# LED_driver_sch.net
KiCad netlist of a schematic drawn in Altium Designer
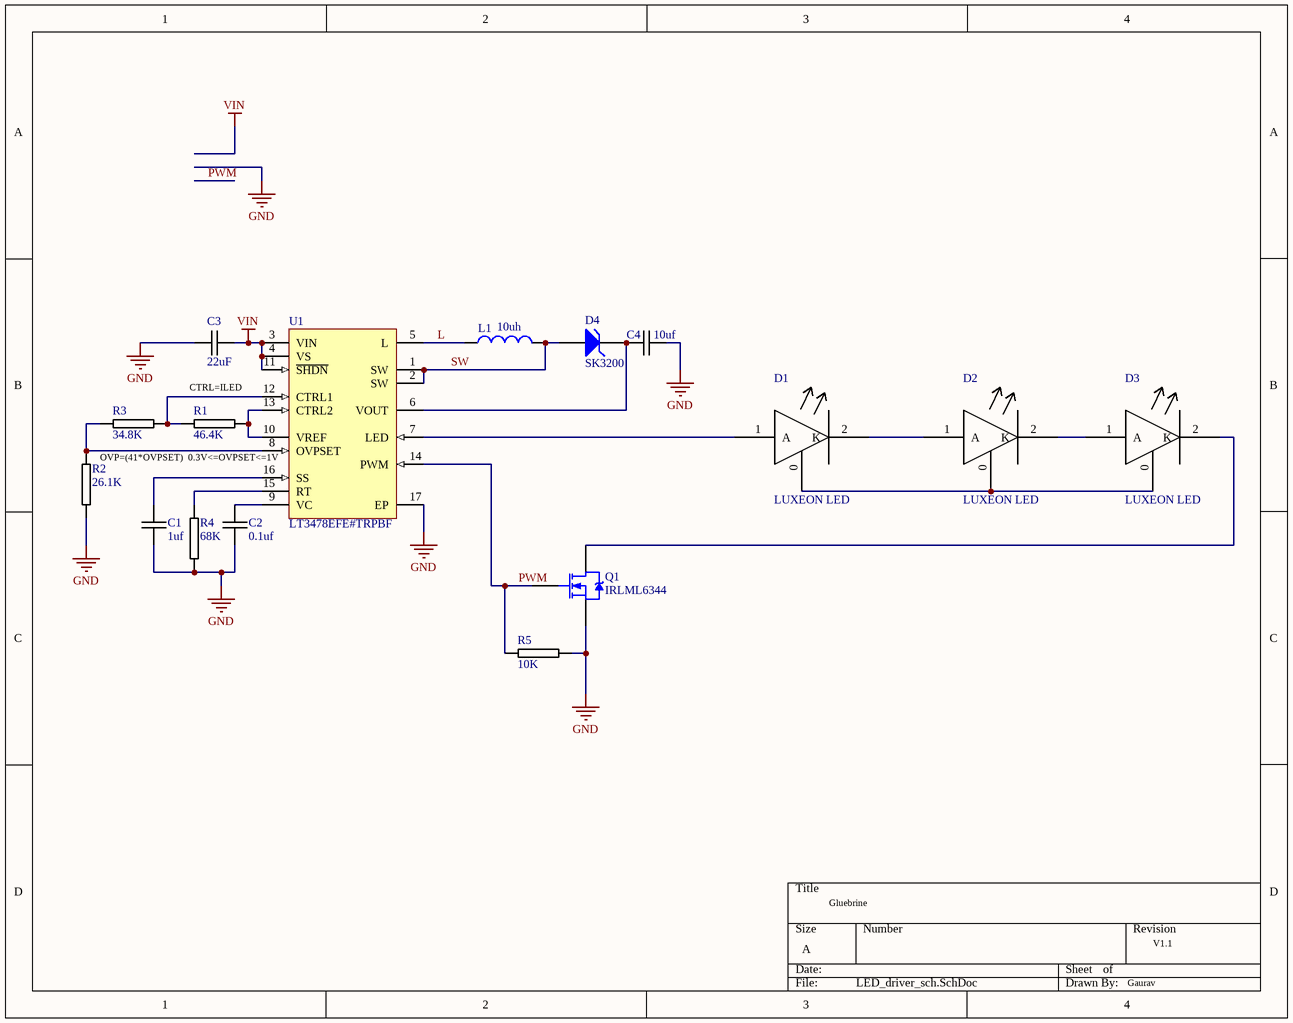
[diagram p0: LED_driver_sch.SchDoc]

(export (version "E")
  (design (tool "Eeschema 10.0.6"))
  (components
    (comp (ref "C1")
      (value "1uf")
      (footprint "0805C-TBD")
      (description "CAPACITOR 0805 CERAMIC VALUE TO BE DETERMINED")
      (libsource (lib "Generic") (part "0805C-TBD"))
    )
    (comp (ref "C2")
      (value "0.1uf")
      (footprint "0805C-TBD")
      (description "CAPACITOR 0805 CERAMIC VALUE TO BE DETERMINED")
      (libsource (lib "Generic") (part "0805C-TBD"))
    )
    (comp (ref "C3")
      (value "22uF")
      (footprint "1210C-GENERIC")
      (description "GENERIC CAPACITOR NON POLARISED 1210")
      (fields
        (field (name "MANUFACTURER") "Panasonic - ECG")
        (field (name "MANUFACTURER PART NUMBER") "ECJ-4YB0J226M")
      )
      (libsource (lib "Generic") (part "1210C-22UF-6V3-X5R-PAN"))
    )
    (comp (ref "C4")
      (value "10uf")
      (footprint "1210C-GENERIC")
      (description "GENERIC CAPACITOR NON POLARISED 1210")
      (fields
        (field (name "MANUFACTURER") "Panasonic - ECG")
        (field (name "MANUFACTURER PART NUMBER") "ECJ-4YB0J226M")
      )
      (libsource (lib "Generic") (part "1210C-22UF-6V3-X5R-PAN"))
    )
    (comp (ref "D1")
      (value "LUXEON LED")
      (footprint "LUXEON")
      (libsource (lib "philips_led") (part "LMX-PWC2"))
    )
    (comp (ref "D2")
      (value "LUXEON LED")
      (footprint "LUXEON")
      (libsource (lib "philips_led") (part "LMX-PWC2"))
    )
    (comp (ref "D3")
      (value "LUXEON LED")
      (footprint "LUXEON")
      (libsource (lib "philips_led") (part "LMX-PWC2"))
    )
    (comp (ref "D4") (value "SK3200") (footprint "SK3200") (libsource (lib "diode") (part "SK3200")))
    (comp (ref "L1") (value "10uh") (footprint "SRR1280A") (libsource (lib "Inductor") (part "inductor_smd")))
    (comp (ref "Q1")
      (value "IRLML6344")
      (footprint "SOT-23_N")
      (description "HEXFET Power MOSFET")
      (fields (field (name "PUBLISHER") "Altium Limited"))
      (libsource (lib "IR Discrete MOSFET - Power") (part "IRLML2402"))
    )
    (comp (ref "R1")
      (value "46.4K")
      (footprint "0805R-TBD")
      (description "RESISTOR 0805 VALUE TO BE DETERMINED")
      (libsource (lib "Generic") (part "0805R-TBD"))
    )
    (comp (ref "R2")
      (value "26.1K")
      (footprint "0805R-TBD")
      (description "RESISTOR 0805 VALUE TO BE DETERMINED")
      (libsource (lib "Generic") (part "0805R-TBD"))
    )
    (comp (ref "R3")
      (value "34.8K")
      (footprint "0805R-TBD")
      (description "RESISTOR 0805 VALUE TO BE DETERMINED")
      (libsource (lib "Generic") (part "0805R-TBD"))
    )
    (comp (ref "R4")
      (value "68K")
      (footprint "0805R-TBD")
      (description "RESISTOR 0805 VALUE TO BE DETERMINED")
      (libsource (lib "Generic") (part "0805R-TBD"))
    )
    (comp (ref "R5")
      (value "10K")
      (footprint "0603R-10K")
      (description "GENERIC RESISTOR 0603")
      (fields (field (name "MANUFACTURER") "Stackpole Electronics Inc") (field (name "TOLERANCE") "±1%"))
      (libsource (lib "Generic") (part "0603R-10K"))
    )
    (comp (ref "U1")
      (value "LT3478EFE#TRPBF")
      (footprint "LT-FE-16-EPV-BC_N")
      (fields (field (name "MANUFACTURER") "Linear Technology"))
      (libsource (lib "Linear Technology Power Management LED Driver ICs") (part "LT3478EFE#TRPBF"))
    )
  )
  (nets
    (net (code "1") (name "/L") (class "Default")
      (node (ref "L1") (pin "1") (pinfunction "1_1") (pintype "passive"))
      (node (ref "U1") (pin "5") (pinfunction "L_5") (pintype "power_in"))
    )
    (net (code "2") (name "/PWM") (class "Default")
      (node (ref "Q1") (pin "1") (pinfunction "G_1") (pintype "passive"))
      (node (ref "R5") (pin "1") (pintype "passive"))
      (node (ref "U1") (pin "14") (pinfunction "PWM_14") (pintype "input"))
    )
    (net (code "3") (name "/SW") (class "Default")
      (node (ref "D4") (pin "1") (pinfunction "A_1") (pintype "passive"))
      (node (ref "L1") (pin "2") (pinfunction "2_2") (pintype "passive"))
      (node (ref "U1") (pin "1") (pinfunction "SW_1") (pintype "power_in"))
      (node (ref "U1") (pin "2") (pinfunction "SW_2") (pintype "power_in"))
    )
    (net (code "4") (name "GND") (class "Default")
      (node (ref "C1") (pin "1") (pintype "passive"))
      (node (ref "C2") (pin "1") (pintype "passive"))
      (node (ref "C3") (pin "2") (pintype "passive"))
      (node (ref "C4") (pin "2") (pintype "passive"))
      (node (ref "Q1") (pin "2") (pinfunction "S_2") (pintype "passive"))
      (node (ref "R2") (pin "2") (pintype "passive"))
      (node (ref "R4") (pin "2") (pintype "passive"))
      (node (ref "R5") (pin "2") (pintype "passive"))
      (node (ref "U1") (pin "17") (pinfunction "EP_17") (pintype "power_in"))
    )
    (net (code "5") (name "Net-(D1-A)") (class "Default")
      (node (ref "D1") (pin "1") (pinfunction "A_1") (pintype "power_in"))
      (node (ref "U1") (pin "7") (pinfunction "LED_7") (pintype "input"))
    )
    (net (code "6") (name "Net-(D1-K)") (class "Default")
      (node (ref "D1") (pin "2") (pinfunction "K_2") (pintype "power_in"))
      (node (ref "D2") (pin "1") (pinfunction "A_1") (pintype "power_in"))
    )
    (net (code "7") (name "Net-(D1-TH)") (class "Default")
      (node (ref "D1") (pin "0") (pinfunction "TH_0") (pintype "passive"))
      (node (ref "D2") (pin "0") (pinfunction "TH_0") (pintype "passive"))
      (node (ref "D3") (pin "0") (pinfunction "TH_0") (pintype "passive"))
    )
    (net (code "8") (name "Net-(D2-K)") (class "Default")
      (node (ref "D2") (pin "2") (pinfunction "K_2") (pintype "power_in"))
      (node (ref "D3") (pin "1") (pinfunction "A_1") (pintype "power_in"))
    )
    (net (code "9") (name "Net-(D3-K)") (class "Default")
      (node (ref "D3") (pin "2") (pinfunction "K_2") (pintype "power_in"))
      (node (ref "Q1") (pin "3") (pinfunction "D_3") (pintype "passive"))
    )
    (net (code "10") (name "Net-(D4-K)") (class "Default")
      (node (ref "C4") (pin "1") (pintype "passive"))
      (node (ref "D4") (pin "2") (pinfunction "K_2") (pintype "passive"))
      (node (ref "U1") (pin "6") (pinfunction "VOUT_6") (pintype "power_in"))
    )
    (net (code "11") (name "Net-(U1-CTRL1)") (class "Default")
      (node (ref "R1") (pin "1") (pintype "passive"))
      (node (ref "R3") (pin "2") (pintype "passive"))
      (node (ref "U1") (pin "12") (pinfunction "CTRL1_12") (pintype "input"))
    )
    (net (code "12") (name "Net-(U1-CTRL2)") (class "Default")
      (node (ref "R1") (pin "2") (pintype "passive"))
      (node (ref "U1") (pin "10") (pinfunction "VREF_10") (pintype "passive"))
      (node (ref "U1") (pin "13") (pinfunction "CTRL2_13") (pintype "input"))
    )
    (net (code "13") (name "Net-(U1-OVPSET)") (class "Default")
      (node (ref "R2") (pin "1") (pintype "passive"))
      (node (ref "R3") (pin "1") (pintype "passive"))
      (node (ref "U1") (pin "8") (pinfunction "OVPSET_8") (pintype "input"))
    )
    (net (code "14") (name "Net-(U1-RT)") (class "Default")
      (node (ref "R4") (pin "1") (pintype "passive"))
      (node (ref "U1") (pin "15") (pinfunction "RT_15") (pintype "passive"))
    )
    (net (code "15") (name "Net-(U1-SS)") (class "Default")
      (node (ref "C1") (pin "2") (pintype "passive"))
      (node (ref "U1") (pin "16") (pinfunction "SS_16") (pintype "input"))
    )
    (net (code "16") (name "Net-(U1-VC)") (class "Default")
      (node (ref "C2") (pin "2") (pintype "passive"))
      (node (ref "U1") (pin "9") (pinfunction "VC_9") (pintype "passive"))
    )
    (net (code "17") (name "VIN") (class "Default")
      (node (ref "C3") (pin "1") (pintype "passive"))
      (node (ref "U1") (pin "11") (pinfunction "~{SHDN}_11") (pintype "input"))
      (node (ref "U1") (pin "3") (pinfunction "VIN_3") (pintype "power_in"))
      (node (ref "U1") (pin "4") (pinfunction "VS_4") (pintype "power_in"))
    )
  )
)
